# M4-Shim-2.net
KiCad netlist of a schematic drawn in EAGLE
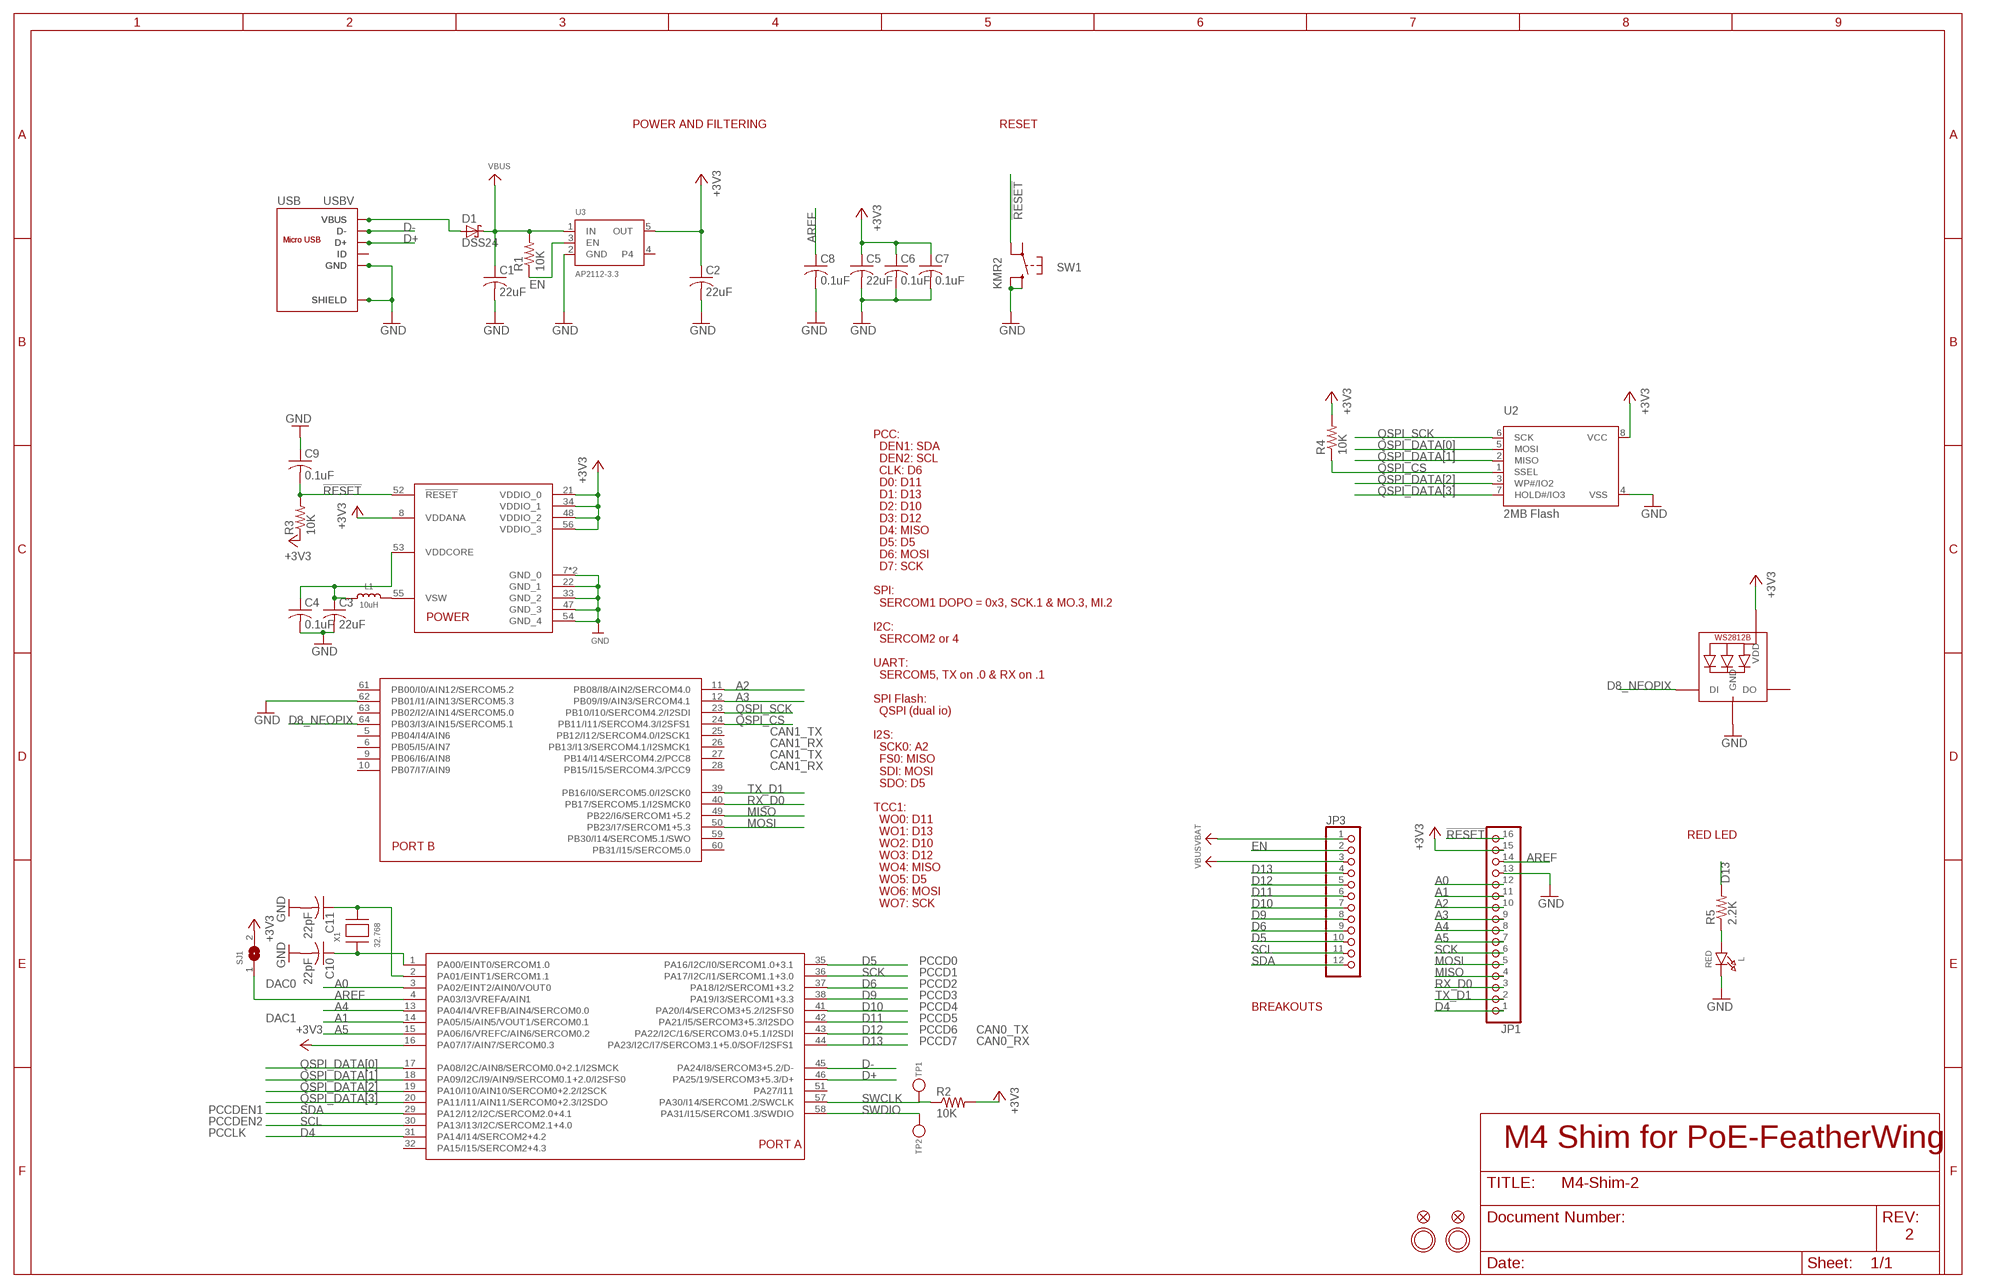
[diagram p0: schematic, sheet 1]

(export (version "E")
  (design (tool "Eeschema 10.0.6"))
  (components
    (comp (ref "C1")
      (value "22uF")
      (footprint "eagle-import:C0805K")
      (libsource (lib "eagle-import") (part "C-USC0805K"))
    )
    (comp (ref "C2")
      (value "22uF")
      (footprint "eagle-import:C0805K")
      (libsource (lib "eagle-import") (part "C-USC0805K"))
    )
    (comp (ref "C3")
      (value "22uF")
      (footprint "eagle-import:C0805K")
      (libsource (lib "eagle-import") (part "C-USC0805K"))
    )
    (comp (ref "C4")
      (value "0.1uF")
      (footprint "eagle-import:C0402K")
      (libsource (lib "eagle-import") (part "C-USC0402K"))
    )
    (comp (ref "C5")
      (value "22uF")
      (footprint "eagle-import:C0805K")
      (libsource (lib "eagle-import") (part "C-USC0805K"))
    )
    (comp (ref "C6")
      (value "0.1uF")
      (footprint "eagle-import:C0402K")
      (libsource (lib "eagle-import") (part "C-USC0402K"))
    )
    (comp (ref "C7")
      (value "0.1uF")
      (footprint "eagle-import:C0402K")
      (libsource (lib "eagle-import") (part "C-USC0402K"))
    )
    (comp (ref "C8")
      (value "0.1uF")
      (footprint "eagle-import:C0402K")
      (libsource (lib "eagle-import") (part "C-USC0402K"))
    )
    (comp (ref "C9")
      (value "0.1uF")
      (footprint "eagle-import:C0402K")
      (libsource (lib "eagle-import") (part "C-USC0402K"))
    )
    (comp (ref "C10")
      (value "22pF")
      (footprint "eagle-import:C0402K")
      (libsource (lib "eagle-import") (part "C-USC0402K"))
    )
    (comp (ref "C11")
      (value "22pF")
      (footprint "eagle-import:C0402K")
      (libsource (lib "eagle-import") (part "C-USC0402K"))
    )
    (comp (ref "D1")
      (value "DSS24")
      (footprint "eagle-import:SOD123FL")
      (libsource (lib "eagle-import") (part "DSS24"))
    )
    (comp (ref "JP1")
      (value "HEADER-1X16ROUND")
      (footprint "eagle-import:1X16_ROUND")
      (libsource (lib "eagle-import") (part "HEADER-1X16ROUND"))
    )
    (comp (ref "JP3")
      (value "HEADER-1X12")
      (footprint "eagle-import:1X12_ROUND")
      (libsource (lib "eagle-import") (part "HEADER-1X12"))
    )
    (comp (ref "L")
      (value "RED")
      (footprint "eagle-import:CHIPLED_0805_NOOUTLINE")
      (libsource (lib "eagle-import") (part "LED0805_NOOUTLINE"))
    )
    (comp (ref "L1")
      (value "10uH")
      (footprint "eagle-import:INDUCTOR_1007")
      (libsource (lib "eagle-import") (part "INDUCTOR"))
    )
    (comp (ref "LED1")
      (value "WS2812B3535")
      (footprint "eagle-import:LED3535")
      (libsource (lib "eagle-import") (part "WS2812B3535"))
    )
    (comp (ref "R1")
      (value "10K")
      (footprint "eagle-import:R0402")
      (libsource (lib "eagle-import") (part "R-US_R0402"))
    )
    (comp (ref "R2")
      (value "10K")
      (footprint "eagle-import:R0402")
      (libsource (lib "eagle-import") (part "R-US_R0402"))
    )
    (comp (ref "R3")
      (value "10K")
      (footprint "eagle-import:R0402")
      (libsource (lib "eagle-import") (part "R-US_R0402"))
    )
    (comp (ref "R4")
      (value "10K")
      (footprint "eagle-import:R0402")
      (libsource (lib "eagle-import") (part "R-US_R0402"))
    )
    (comp (ref "R5")
      (value "2.2K")
      (footprint "eagle-import:R0402")
      (libsource (lib "eagle-import") (part "R-US_R0402"))
    )
    (comp (ref "SJ1")
      (value "SOLDERJUMPERCLOSED")
      (footprint "eagle-import:SOLDERJUMPER_CLOSEDWIRE")
      (libsource (lib "eagle-import") (part "SOLDERJUMPERCLOSED"))
    )
    (comp (ref "SW1")
      (value "KMR2")
      (footprint "eagle-import:BTN_KMR2_4.6X2.8")
      (libsource (lib "eagle-import") (part "SWITCH_TACT_SMT4.6X2.8"))
    )
    (comp (ref "TP1")
      (value "TESTPOINTROUND1.5MM")
      (footprint "eagle-import:TESTPOINT_ROUND_1.5MM")
      (libsource (lib "eagle-import") (part "TESTPOINTROUND1.5MM"))
    )
    (comp (ref "TP2")
      (value "TESTPOINTROUND1.5MM")
      (footprint "eagle-import:TESTPOINT_ROUND_1.5MM")
      (libsource (lib "eagle-import") (part "TESTPOINTROUND1.5MM"))
    )
    (comp (ref "U$31")
      (value "MOUNTINGHOLE2.5")
      (footprint "eagle-import:MOUNTINGHOLE_2.5_PLATED")
      (libsource (lib "eagle-import") (part "MOUNTINGHOLE2.5"))
    )
    (comp (ref "U$32")
      (value "MOUNTINGHOLE2.5")
      (footprint "eagle-import:MOUNTINGHOLE_2.5_PLATED")
      (libsource (lib "eagle-import") (part "MOUNTINGHOLE2.5"))
    )
    (comp (ref "U$34")
      (value "FIDUCIAL_1MM")
      (footprint "eagle-import:FIDUCIAL_1MM")
      (libsource (lib "eagle-import") (part "FIDUCIAL_1MM"))
    )
    (comp (ref "U$35")
      (value "FIDUCIAL_1MM")
      (footprint "eagle-import:FIDUCIAL_1MM")
      (libsource (lib "eagle-import") (part "FIDUCIAL_1MM"))
    )
    (comp (ref "U1")
      (value "ATSAMD51J")
      (footprint "eagle-import:PQFN64-1")
      (libsource (lib "eagle-import") (part "ATSAMD51J"))
    )
    (comp (ref "U2")
      (value "2MB Flash")
      (footprint "eagle-import:USON8")
      (libsource (lib "eagle-import") (part "SPIFLASH_8PINUX"))
    )
    (comp (ref "U3")
      (value "AP2112-3.3")
      (footprint "eagle-import:SOT23-5")
      (libsource (lib "eagle-import") (part "VREG_SOT23-5"))
    )
    (comp (ref "USB")
      (value "ZX62-B-5PA")
      (footprint "eagle-import:TS-1012E-AC03516")
      (libsource (lib "eagle-import") (part "MICRO-USB-SMD"))
    )
    (comp (ref "USBV")
      (value "MICRO-USB-SMD-VERT")
      (footprint "eagle-import:U-D-M5DS-W-4")
      (libsource (lib "eagle-import") (part "MICRO-USB-SMD-VERT"))
    )
    (comp (ref "X1")
      (value "32.768")
      (footprint "eagle-import:XTAL3215")
      (libsource (lib "eagle-import") (part "XTAL-3.2X1.5"))
    )
  )
  (nets
    (net (code "1") (name "+3V3") (class "Default")
      (node (ref "C2") (pin "1") (pinfunction "1_1") (pintype "passive"))
      (node (ref "C5") (pin "1") (pinfunction "1_1") (pintype "passive"))
      (node (ref "C6") (pin "1") (pinfunction "1_1") (pintype "passive"))
      (node (ref "C7") (pin "1") (pinfunction "1_1") (pintype "passive"))
      (node (ref "JP1") (pin "15") (pinfunction "15_15") (pintype "passive"))
      (node (ref "LED1") (pin "2") (pinfunction "VDD_2") (pintype "power_in"))
      (node (ref "R2") (pin "2") (pinfunction "2_2") (pintype "passive"))
      (node (ref "R3") (pin "1") (pinfunction "1_1") (pintype "passive"))
      (node (ref "R4") (pin "2") (pinfunction "2_2") (pintype "passive"))
      (node (ref "SJ1") (pin "2") (pinfunction "2_2") (pintype "passive"))
      (node (ref "U1") (pin "16") (pinfunction "PA07/I7/AIN7/SERCOM0.3_16") (pintype "bidirectional"))
      (node (ref "U1") (pin "21") (pinfunction "VDDIO_0_21") (pintype "bidirectional"))
      (node (ref "U1") (pin "34") (pinfunction "VDDIO_1_34") (pintype "bidirectional"))
      (node (ref "U1") (pin "48") (pinfunction "VDDIO_2_48") (pintype "bidirectional"))
      (node (ref "U1") (pin "56") (pinfunction "VDDIO_3_56") (pintype "bidirectional"))
      (node (ref "U1") (pin "8") (pinfunction "VDDANA_8") (pintype "bidirectional"))
      (node (ref "U2") (pin "8") (pinfunction "VCC_8") (pintype "bidirectional"))
      (node (ref "U3") (pin "5") (pinfunction "OUT_5") (pintype "power_in"))
    )
    (net (code "2") (name "/A0") (class "Default")
      (node (ref "JP1") (pin "12") (pinfunction "12_12") (pintype "passive"))
      (node (ref "U1") (pin "3") (pinfunction "PA02/EINT2/AIN0/VOUT0_3") (pintype "bidirectional"))
    )
    (net (code "3") (name "/A1") (class "Default")
      (node (ref "JP1") (pin "11") (pinfunction "11_11") (pintype "passive"))
      (node (ref "U1") (pin "14") (pinfunction "PA05/I5/AIN5/VOUT1/SERCOM0.1_14") (pintype "bidirectional"))
    )
    (net (code "4") (name "/A2") (class "Default")
      (node (ref "JP1") (pin "10") (pinfunction "10_10") (pintype "passive"))
      (node (ref "U1") (pin "11") (pinfunction "PB08/I8/AIN2/SERCOM4.0_11") (pintype "bidirectional"))
    )
    (net (code "5") (name "/A3") (class "Default")
      (node (ref "JP1") (pin "9") (pinfunction "9_9") (pintype "passive"))
      (node (ref "U1") (pin "12") (pinfunction "PB09/I9/AIN3/SERCOM4.1_12") (pintype "bidirectional"))
    )
    (net (code "6") (name "/A4") (class "Default")
      (node (ref "JP1") (pin "8") (pinfunction "8_8") (pintype "passive"))
      (node (ref "U1") (pin "13") (pinfunction "PA04/I4/VREFB/AIN4/SERCOM0.0_13") (pintype "bidirectional"))
    )
    (net (code "7") (name "/A5") (class "Default")
      (node (ref "JP1") (pin "7") (pinfunction "7_7") (pintype "passive"))
      (node (ref "U1") (pin "15") (pinfunction "PA06/I6/VREFC/AIN6/SERCOM0.2_15") (pintype "bidirectional"))
    )
    (net (code "8") (name "/AREF") (class "Default")
      (node (ref "C8") (pin "1") (pinfunction "1_1") (pintype "passive"))
      (node (ref "JP1") (pin "14") (pinfunction "14_14") (pintype "passive"))
      (node (ref "SJ1") (pin "1") (pinfunction "1_1") (pintype "passive"))
      (node (ref "U1") (pin "4") (pinfunction "PA03/I3/VREFA/AIN1_4") (pintype "bidirectional"))
    )
    (net (code "9") (name "/D+") (class "Default")
      (node (ref "U1") (pin "46") (pinfunction "PA25/19/SERCOM3+5.3/D+_46") (pintype "bidirectional"))
      (node (ref "USB") (pin "3") (pinfunction "D+_3") (pintype "bidirectional"))
      (node (ref "USBV") (pin "3") (pinfunction "D+_3") (pintype "bidirectional"))
    )
    (net (code "10") (name "/D-") (class "Default")
      (node (ref "U1") (pin "45") (pinfunction "PA24/I8/SERCOM3+5.2/D-_45") (pintype "bidirectional"))
      (node (ref "USB") (pin "2") (pinfunction "D-_2") (pintype "bidirectional"))
      (node (ref "USBV") (pin "2") (pinfunction "D-_2") (pintype "bidirectional"))
    )
    (net (code "11") (name "/D4") (class "Default")
      (node (ref "JP1") (pin "1") (pinfunction "1_1") (pintype "passive"))
      (node (ref "U1") (pin "31") (pinfunction "PA14/I14/SERCOM2+4.2_31") (pintype "bidirectional"))
    )
    (net (code "12") (name "/D5") (class "Default")
      (node (ref "JP3") (pin "10") (pinfunction "10_10") (pintype "passive"))
      (node (ref "U1") (pin "35") (pinfunction "PA16/I2C/I0/SERCOM1.0+3.1_35") (pintype "bidirectional"))
    )
    (net (code "13") (name "/D6") (class "Default")
      (node (ref "JP3") (pin "9") (pinfunction "9_9") (pintype "passive"))
      (node (ref "U1") (pin "37") (pinfunction "PA18/I2/SERCOM1+3.2_37") (pintype "bidirectional"))
    )
    (net (code "14") (name "/D8_NEOPIX") (class "Default")
      (node (ref "LED1") (pin "1") (pinfunction "DI_1") (pintype "input"))
      (node (ref "U1") (pin "64") (pinfunction "PB03/I3/AIN15/SERCOM5.1_64") (pintype "bidirectional"))
    )
    (net (code "15") (name "/D9") (class "Default")
      (node (ref "JP3") (pin "8") (pinfunction "8_8") (pintype "passive"))
      (node (ref "U1") (pin "38") (pinfunction "PA19/I3/SERCOM1+3.3_38") (pintype "bidirectional"))
    )
    (net (code "16") (name "/D10") (class "Default")
      (node (ref "JP3") (pin "7") (pinfunction "7_7") (pintype "passive"))
      (node (ref "U1") (pin "41") (pinfunction "PA20/I4/SERCOM3+5.2/I2SFS0_41") (pintype "bidirectional"))
    )
    (net (code "17") (name "/D11") (class "Default")
      (node (ref "JP3") (pin "6") (pinfunction "6_6") (pintype "passive"))
      (node (ref "U1") (pin "42") (pinfunction "PA21/I5/SERCOM3+5.3/I2SDO_42") (pintype "bidirectional"))
    )
    (net (code "18") (name "/D12") (class "Default")
      (node (ref "JP3") (pin "5") (pinfunction "5_5") (pintype "passive"))
      (node (ref "U1") (pin "43") (pinfunction "PA22/I2C/16/SERCOM3.0+5.1/I2SDI_43") (pintype "bidirectional"))
    )
    (net (code "19") (name "/D13") (class "Default")
      (node (ref "JP3") (pin "4") (pinfunction "4_4") (pintype "passive"))
      (node (ref "R5") (pin "2") (pinfunction "2_2") (pintype "passive"))
      (node (ref "U1") (pin "44") (pinfunction "PA23/I2C/I7/SERCOM3.1+5.0/SOF/I2SFS1_44") (pintype "bidirectional"))
    )
    (net (code "20") (name "/EN") (class "Default")
      (node (ref "JP3") (pin "2") (pinfunction "2_2") (pintype "passive"))
      (node (ref "R1") (pin "1") (pinfunction "1_1") (pintype "passive"))
      (node (ref "U3") (pin "3") (pinfunction "EN_3") (pintype "input"))
    )
    (net (code "21") (name "/MISO") (class "Default")
      (node (ref "JP1") (pin "4") (pinfunction "4_4") (pintype "passive"))
      (node (ref "U1") (pin "49") (pinfunction "PB22/I6/SERCOM1+5.2_49") (pintype "bidirectional"))
    )
    (net (code "22") (name "/MOSI") (class "Default")
      (node (ref "JP1") (pin "5") (pinfunction "5_5") (pintype "passive"))
      (node (ref "U1") (pin "50") (pinfunction "PB23/I7/SERCOM1+5.3_50") (pintype "bidirectional"))
    )
    (net (code "23") (name "/QSPI_CS") (class "Default")
      (node (ref "R4") (pin "1") (pinfunction "1_1") (pintype "passive"))
      (node (ref "U1") (pin "24") (pinfunction "PB11/I11/SERCOM4.3/I2SFS1_24") (pintype "bidirectional"))
      (node (ref "U2") (pin "1") (pinfunction "SSEL_1") (pintype "bidirectional"))
    )
    (net (code "24") (name "/QSPI_DATA[0]") (class "Default")
      (node (ref "U1") (pin "17") (pinfunction "PA08/I2C/AIN8/SERCOM0.0+2.1/I2SMCK_17") (pintype "bidirectional"))
      (node (ref "U2") (pin "5") (pinfunction "MOSI_5") (pintype "bidirectional"))
    )
    (net (code "25") (name "/QSPI_DATA[1]") (class "Default")
      (node (ref "U1") (pin "18") (pinfunction "PA09/I2C/I9/AIN9/SERCOM0.1+2.0/I2SFS0_18") (pintype "bidirectional"))
      (node (ref "U2") (pin "2") (pinfunction "MISO_2") (pintype "bidirectional"))
    )
    (net (code "26") (name "/QSPI_DATA[2]") (class "Default")
      (node (ref "U1") (pin "19") (pinfunction "PA10/I10/AIN10/SERCOM0+2.2/I2SCK_19") (pintype "bidirectional"))
      (node (ref "U2") (pin "3") (pinfunction "WP#/IO2_3") (pintype "bidirectional"))
    )
    (net (code "27") (name "/QSPI_DATA[3]") (class "Default")
      (node (ref "U1") (pin "20") (pinfunction "PA11/I11/AIN11/SERCOM0+2.3/I2SDO_20") (pintype "bidirectional"))
      (node (ref "U2") (pin "7") (pinfunction "HOLD#/IO3_7") (pintype "bidirectional"))
    )
    (net (code "28") (name "/QSPI_SCK") (class "Default")
      (node (ref "U1") (pin "23") (pinfunction "PB10/I10/SERCOM4.2/I2SDI_23") (pintype "bidirectional"))
      (node (ref "U2") (pin "6") (pinfunction "SCK_6") (pintype "bidirectional"))
    )
    (net (code "29") (name "/RX_D0") (class "Default")
      (node (ref "JP1") (pin "3") (pinfunction "3_3") (pintype "passive"))
      (node (ref "U1") (pin "40") (pinfunction "PB17/SERCOM5.1/I2SMCK0_40") (pintype "bidirectional"))
    )
    (net (code "30") (name "/SCK") (class "Default")
      (node (ref "JP1") (pin "6") (pinfunction "6_6") (pintype "passive"))
      (node (ref "U1") (pin "36") (pinfunction "PA17/I2C/I1/SERCOM1.1+3.0_36") (pintype "bidirectional"))
    )
    (net (code "31") (name "/SCL") (class "Default")
      (node (ref "JP3") (pin "11") (pinfunction "11_11") (pintype "passive"))
      (node (ref "U1") (pin "30") (pinfunction "PA13/I13/I2C/SERCOM2.1+4.0_30") (pintype "bidirectional"))
    )
    (net (code "32") (name "/SDA") (class "Default")
      (node (ref "JP3") (pin "12") (pinfunction "12_12") (pintype "passive"))
      (node (ref "U1") (pin "29") (pinfunction "PA12/I12/I2C/SERCOM2.0+4.1_29") (pintype "bidirectional"))
    )
    (net (code "33") (name "/SWCLK") (class "Default")
      (node (ref "R2") (pin "1") (pinfunction "1_1") (pintype "passive"))
      (node (ref "TP1") (pin "P$1") (pinfunction "P$1_P$1") (pintype "bidirectional"))
      (node (ref "U1") (pin "57") (pinfunction "PA30/I14/SERCOM1.2/SWCLK_57") (pintype "bidirectional"))
    )
    (net (code "34") (name "/SWDIO") (class "Default")
      (node (ref "TP2") (pin "P$1") (pinfunction "P$1_P$1") (pintype "bidirectional"))
      (node (ref "U1") (pin "58") (pinfunction "PA31/I15/SERCOM1.3/SWDIO_58") (pintype "bidirectional"))
    )
    (net (code "35") (name "/TX_D1") (class "Default")
      (node (ref "JP1") (pin "2") (pinfunction "2_2") (pintype "passive"))
      (node (ref "U1") (pin "39") (pinfunction "PB16/I0/SERCOM5.0/I2SCK0_39") (pintype "bidirectional"))
    )
    (net (code "36") (name "/~{RESET}") (class "Default")
      (node (ref "C9") (pin "2") (pinfunction "2_2") (pintype "passive"))
      (node (ref "JP1") (pin "16") (pinfunction "16_16") (pintype "passive"))
      (node (ref "R3") (pin "2") (pinfunction "2_2") (pintype "passive"))
      (node (ref "SW1") (pin "A'") (pinfunction "P1_A'") (pintype "passive"))
      (node (ref "U1") (pin "52") (pinfunction "~{RESET}_52") (pintype "bidirectional"))
    )
    (net (code "37") (name "GND") (class "Default")
      (node (ref "C1") (pin "2") (pinfunction "2_2") (pintype "passive"))
      (node (ref "C10") (pin "2") (pinfunction "2_2") (pintype "passive"))
      (node (ref "C11") (pin "2") (pinfunction "2_2") (pintype "passive"))
      (node (ref "C2") (pin "2") (pinfunction "2_2") (pintype "passive"))
      (node (ref "C3") (pin "2") (pinfunction "2_2") (pintype "passive"))
      (node (ref "C4") (pin "2") (pinfunction "2_2") (pintype "passive"))
      (node (ref "C5") (pin "2") (pinfunction "2_2") (pintype "passive"))
      (node (ref "C6") (pin "2") (pinfunction "2_2") (pintype "passive"))
      (node (ref "C7") (pin "2") (pinfunction "2_2") (pintype "passive"))
      (node (ref "C8") (pin "2") (pinfunction "2_2") (pintype "passive"))
      (node (ref "C9") (pin "1") (pinfunction "1_1") (pintype "passive"))
      (node (ref "JP1") (pin "13") (pinfunction "13_13") (pintype "passive"))
      (node (ref "L") (pin "C") (pinfunction "C_C") (pintype "passive"))
      (node (ref "LED1") (pin "4") (pinfunction "GND_4") (pintype "power_in"))
      (node (ref "SW1") (pin "B") (pinfunction "S_B") (pintype "passive"))
      (node (ref "SW1") (pin "B'") (pinfunction "S1_B'") (pintype "passive"))
      (node (ref "U1") (pin "22") (pinfunction "GND_1_22") (pintype "bidirectional"))
      (node (ref "U1") (pin "33") (pinfunction "GND_2_33") (pintype "bidirectional"))
      (node (ref "U1") (pin "47") (pinfunction "GND_3_47") (pintype "bidirectional"))
      (node (ref "U1") (pin "54") (pinfunction "GND_4_54") (pintype "bidirectional"))
      (node (ref "U1") (pin "62") (pinfunction "PB01/I1/AIN13/SERCOM5.3_62") (pintype "bidirectional"))
      (node (ref "U1") (pin "7") (pinfunction "GND_0_7") (pintype "bidirectional"))
      (node (ref "U1") (pin "EXP") (pinfunction "GND_0_EXP") (pintype "bidirectional"))
      (node (ref "U2") (pin "4") (pinfunction "VSS_4") (pintype "bidirectional"))
      (node (ref "U3") (pin "2") (pinfunction "GND_2") (pintype "power_in"))
      (node (ref "USB") (pin "5") (pinfunction "GND_5") (pintype "power_in"))
      (node (ref "USB") (pin "P1") (pinfunction "SHIELD_P1") (pintype "power_in"))
      (node (ref "USB") (pin "P2") (pinfunction "SHIELD_P2") (pintype "power_in"))
      (node (ref "USB") (pin "P3") (pinfunction "SHIELD_P3") (pintype "power_in"))
      (node (ref "USB") (pin "P4") (pinfunction "SHIELD_P4") (pintype "power_in"))
      (node (ref "USB") (pin "P5") (pinfunction "SHIELD_P5") (pintype "power_in"))
      (node (ref "USB") (pin "P6") (pinfunction "SHIELD_P6") (pintype "power_in"))
      (node (ref "USBV") (pin "5") (pinfunction "GND_5") (pintype "power_in"))
      (node (ref "USBV") (pin "MNT1") (pinfunction "SHIELD_MNT1") (pintype "power_in"))
      (node (ref "USBV") (pin "MNT2") (pinfunction "SHIELD_MNT2") (pintype "power_in"))
      (node (ref "USBV") (pin "MNT3") (pinfunction "SHIELD_MNT3") (pintype "power_in"))
      (node (ref "USBV") (pin "MNT4") (pinfunction "SHIELD_MNT4") (pintype "power_in"))
    )
    (net (code "38") (name "Net-(L-PadA)") (class "Default")
      (node (ref "L") (pin "A") (pinfunction "A_A") (pintype "passive"))
      (node (ref "R5") (pin "1") (pinfunction "1_1") (pintype "passive"))
    )
    (net (code "39") (name "Net-(L1-1)") (class "Default")
      (node (ref "C3") (pin "1") (pinfunction "1_1") (pintype "passive"))
      (node (ref "C4") (pin "1") (pinfunction "1_1") (pintype "passive"))
      (node (ref "L1") (pin "P$1") (pinfunction "1_P$1") (pintype "passive"))
      (node (ref "U1") (pin "53") (pinfunction "VDDCORE_53") (pintype "bidirectional"))
    )
    (net (code "40") (name "Net-(L1-2)") (class "Default")
      (node (ref "L1") (pin "P$2") (pinfunction "2_P$2") (pintype "passive"))
      (node (ref "U1") (pin "55") (pinfunction "VSW_55") (pintype "bidirectional"))
    )
    (net (code "41") (name "Net-(U1A-PA00{slash}EINT0{slash}SERCOM1.0)") (class "Default")
      (node (ref "C10") (pin "1") (pinfunction "1_1") (pintype "passive"))
      (node (ref "U1") (pin "1") (pinfunction "PA00/EINT0/SERCOM1.0_1") (pintype "bidirectional"))
      (node (ref "X1") (pin "P$1") (pinfunction "P$1_P$1") (pintype "bidirectional"))
    )
    (net (code "42") (name "Net-(U1A-PA01{slash}EINT1{slash}SERCOM1.1)") (class "Default")
      (node (ref "C11") (pin "1") (pinfunction "1_1") (pintype "passive"))
      (node (ref "U1") (pin "2") (pinfunction "PA01/EINT1/SERCOM1.1_2") (pintype "bidirectional"))
      (node (ref "X1") (pin "P$2") (pinfunction "P$2_P$2") (pintype "bidirectional"))
    )
    (net (code "43") (name "Net-(USB-ID)") (class "Default")
      (node (ref "USB") (pin "4") (pinfunction "ID_4") (pintype "bidirectional"))
      (node (ref "USBV") (pin "4") (pinfunction "ID_4") (pintype "bidirectional"))
    )
    (net (code "44") (name "Net-(USB-VBUS)") (class "Default")
      (node (ref "D1") (pin "A") (pinfunction "A_A") (pintype "passive"))
      (node (ref "USB") (pin "1") (pinfunction "VBUS_1") (pintype "power_in"))
      (node (ref "USBV") (pin "1") (pinfunction "VBUS_1") (pintype "power_in"))
    )
    (net (code "45") (name "VBAT") (class "Default")
      (node (ref "JP3") (pin "1") (pinfunction "1_1") (pintype "passive"))
    )
    (net (code "46") (name "VBUS") (class "Default")
      (node (ref "C1") (pin "1") (pinfunction "1_1") (pintype "passive"))
      (node (ref "D1") (pin "C") (pinfunction "C_C") (pintype "passive"))
      (node (ref "JP3") (pin "3") (pinfunction "3_3") (pintype "passive"))
      (node (ref "R1") (pin "2") (pinfunction "2_2") (pintype "passive"))
      (node (ref "U3") (pin "1") (pinfunction "IN_1") (pintype "power_in"))
    )
    (net (code "47") (name "unconnected-(LED1-DO-Pad3)") (class "Default")
      (node (ref "LED1") (pin "3") (pinfunction "DO_3") (pintype "output"))
    )
    (net (code "48") (name "unconnected-(SW1-P-PadA)") (class "Default")
      (node (ref "SW1") (pin "A") (pinfunction "P_A") (pintype "passive"))
    )
    (net (code "49") (name "unconnected-(U1A-PA15{slash}I15{slash}SERCOM2+4.3-Pad32)") (class "Default")
      (node (ref "U1") (pin "32") (pinfunction "PA15/I15/SERCOM2+4.3_32") (pintype "bidirectional"))
    )
    (net (code "50") (name "unconnected-(U1A-PA27{slash}I11-Pad51)") (class "Default")
      (node (ref "U1") (pin "51") (pinfunction "PA27/I11_51") (pintype "bidirectional"))
    )
    (net (code "51") (name "unconnected-(U1B-PB00{slash}I0{slash}AIN12{slash}SERCOM5.2-Pad61)") (class "Default")
      (node (ref "U1") (pin "61") (pinfunction "PB00/I0/AIN12/SERCOM5.2_61") (pintype "bidirectional"))
    )
    (net (code "52") (name "unconnected-(U1B-PB02{slash}I2{slash}AIN14{slash}SERCOM5.0-Pad63)") (class "Default")
      (node (ref "U1") (pin "63") (pinfunction "PB02/I2/AIN14/SERCOM5.0_63") (pintype "bidirectional"))
    )
    (net (code "53") (name "unconnected-(U1B-PB04{slash}I4{slash}AIN6-Pad5)") (class "Default")
      (node (ref "U1") (pin "5") (pinfunction "PB04/I4/AIN6_5") (pintype "bidirectional"))
    )
    (net (code "54") (name "unconnected-(U1B-PB05{slash}I5{slash}AIN7-Pad6)") (class "Default")
      (node (ref "U1") (pin "6") (pinfunction "PB05/I5/AIN7_6") (pintype "bidirectional"))
    )
    (net (code "55") (name "unconnected-(U1B-PB06{slash}I6{slash}AIN8-Pad9)") (class "Default")
      (node (ref "U1") (pin "9") (pinfunction "PB06/I6/AIN8_9") (pintype "bidirectional"))
    )
    (net (code "56") (name "unconnected-(U1B-PB07{slash}I7{slash}AIN9-Pad10)") (class "Default")
      (node (ref "U1") (pin "10") (pinfunction "PB07/I7/AIN9_10") (pintype "bidirectional"))
    )
    (net (code "57") (name "unconnected-(U1B-PB12{slash}I12{slash}SERCOM4.0{slash}I2SCK1-Pad25)") (class "Default")
      (node (ref "U1") (pin "25") (pinfunction "PB12/I12/SERCOM4.0/I2SCK1_25") (pintype "bidirectional"))
    )
    (net (code "58") (name "unconnected-(U1B-PB13{slash}I13{slash}SERCOM4.1{slash}I2SMCK1-Pad26)") (class "Default")
      (node (ref "U1") (pin "26") (pinfunction "PB13/I13/SERCOM4.1/I2SMCK1_26") (pintype "bidirectional"))
    )
    (net (code "59") (name "unconnected-(U1B-PB14{slash}I14{slash}SERCOM4.2{slash}PCC8-Pad27)") (class "Default")
      (node (ref "U1") (pin "27") (pinfunction "PB14/I14/SERCOM4.2/PCC8_27") (pintype "bidirectional"))
    )
    (net (code "60") (name "unconnected-(U1B-PB15{slash}I15{slash}SERCOM4.3{slash}PCC9-Pad28)") (class "Default")
      (node (ref "U1") (pin "28") (pinfunction "PB15/I15/SERCOM4.3/PCC9_28") (pintype "bidirectional"))
    )
    (net (code "61") (name "unconnected-(U1B-PB30{slash}I14{slash}SERCOM5.1{slash}SWO-Pad59)") (class "Default")
      (node (ref "U1") (pin "59") (pinfunction "PB30/I14/SERCOM5.1/SWO_59") (pintype "bidirectional"))
    )
    (net (code "62") (name "unconnected-(U1B-PB31{slash}I15{slash}SERCOM5.0-Pad60)") (class "Default")
      (node (ref "U1") (pin "60") (pinfunction "PB31/I15/SERCOM5.0_60") (pintype "bidirectional"))
    )
    (net (code "63") (name "unconnected-(U3-P4-Pad4)") (class "Default")
      (node (ref "U3") (pin "4") (pinfunction "P4_4") (pintype "bidirectional"))
    )
  )
)
